# 600_V1_0.net
KiCad netlist of a schematic drawn in Altium Designer
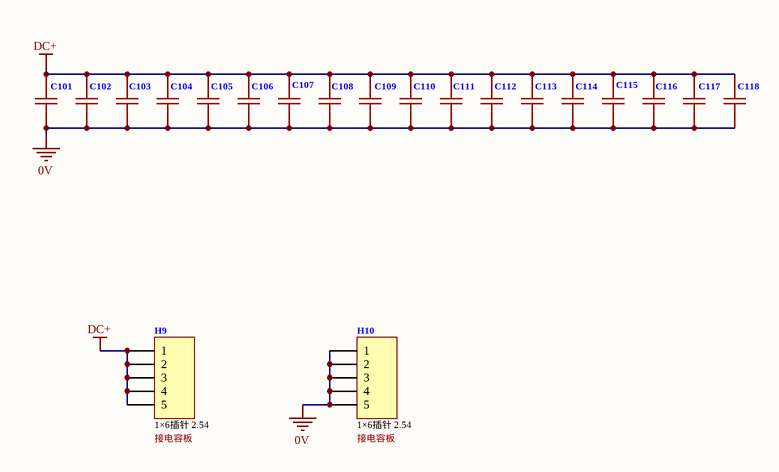
[diagram p0: 600米舵机电容板V1.0.SchDoc]

(export (version "E")
  (design (tool "Eeschema 10.0.6"))
  (components
    (comp (ref "C101")
      (value "4.7uf 100V")
      (footprint "1210_C")
      (description "贴片电容")
      (fields (field (name "MANUFACTURER") "FH(风华)") (field (name "MANUFACTURER PART") "1210B475K101NT"))
      (libsource (lib "Schlib1") (part "1210 4.7uf"))
    )
    (comp (ref "C102")
      (value "4.7uf 100V")
      (footprint "1210_C")
      (description "贴片电容")
      (fields (field (name "MANUFACTURER") "FH(风华)") (field (name "MANUFACTURER PART") "1210B475K101NT"))
      (libsource (lib "Schlib1") (part "1210 4.7uf"))
    )
    (comp (ref "C103")
      (value "4.7uf 100V")
      (footprint "1210_C")
      (description "贴片电容")
      (fields (field (name "MANUFACTURER") "FH(风华)") (field (name "MANUFACTURER PART") "1210B475K101NT"))
      (libsource (lib "Schlib1") (part "1210 4.7uf"))
    )
    (comp (ref "C104")
      (value "4.7uf 100V")
      (footprint "1210_C")
      (description "贴片电容")
      (fields (field (name "MANUFACTURER") "FH(风华)") (field (name "MANUFACTURER PART") "1210B475K101NT"))
      (libsource (lib "Schlib1") (part "1210 4.7uf"))
    )
    (comp (ref "C105")
      (value "4.7uf 100V")
      (footprint "1210_C")
      (description "贴片电容")
      (fields (field (name "MANUFACTURER") "FH(风华)") (field (name "MANUFACTURER PART") "1210B475K101NT"))
      (libsource (lib "Schlib1") (part "1210 4.7uf"))
    )
    (comp (ref "C106")
      (value "4.7uf 100V")
      (footprint "1210_C")
      (description "贴片电容")
      (fields (field (name "MANUFACTURER") "FH(风华)") (field (name "MANUFACTURER PART") "1210B475K101NT"))
      (libsource (lib "Schlib1") (part "1210 4.7uf"))
    )
    (comp (ref "C107")
      (value "4.7uf 100V")
      (footprint "1210_C")
      (description "贴片电容")
      (fields (field (name "MANUFACTURER") "FH(风华)") (field (name "MANUFACTURER PART") "1210B475K101NT"))
      (libsource (lib "Schlib1") (part "1210 4.7uf"))
    )
    (comp (ref "C108")
      (value "4.7uf 100V")
      (footprint "1210_C")
      (description "贴片电容")
      (fields (field (name "MANUFACTURER") "FH(风华)") (field (name "MANUFACTURER PART") "1210B475K101NT"))
      (libsource (lib "Schlib1") (part "1210 4.7uf"))
    )
    (comp (ref "C109")
      (value "4.7uf 100V")
      (footprint "1210_C")
      (description "贴片电容")
      (fields (field (name "MANUFACTURER") "FH(风华)") (field (name "MANUFACTURER PART") "1210B475K101NT"))
      (libsource (lib "Schlib1") (part "1210 4.7uf"))
    )
    (comp (ref "C110")
      (value "4.7uf 100V")
      (footprint "1210_C")
      (description "贴片电容")
      (fields (field (name "MANUFACTURER") "FH(风华)") (field (name "MANUFACTURER PART") "1210B475K101NT"))
      (libsource (lib "Schlib1") (part "1210 4.7uf"))
    )
    (comp (ref "C111")
      (value "4.7uf 100V")
      (footprint "1210_C")
      (description "贴片电容")
      (fields (field (name "MANUFACTURER") "FH(风华)") (field (name "MANUFACTURER PART") "1210B475K101NT"))
      (libsource (lib "Schlib1") (part "1210 4.7uf"))
    )
    (comp (ref "C112")
      (value "4.7uf 100V")
      (footprint "1210_C")
      (description "贴片电容")
      (fields (field (name "MANUFACTURER") "FH(风华)") (field (name "MANUFACTURER PART") "1210B475K101NT"))
      (libsource (lib "Schlib1") (part "1210 4.7uf"))
    )
    (comp (ref "C113")
      (value "4.7uf 100V")
      (footprint "1210_C")
      (description "贴片电容")
      (fields (field (name "MANUFACTURER") "FH(风华)") (field (name "MANUFACTURER PART") "1210B475K101NT"))
      (libsource (lib "Schlib1") (part "1210 4.7uf"))
    )
    (comp (ref "C114")
      (value "4.7uf 100V")
      (footprint "1210_C")
      (description "贴片电容")
      (fields (field (name "MANUFACTURER") "FH(风华)") (field (name "MANUFACTURER PART") "1210B475K101NT"))
      (libsource (lib "Schlib1") (part "1210 4.7uf"))
    )
    (comp (ref "C115")
      (value "4.7uf 100V")
      (footprint "1210_C")
      (description "贴片电容")
      (fields (field (name "MANUFACTURER") "FH(风华)") (field (name "MANUFACTURER PART") "1210B475K101NT"))
      (libsource (lib "Schlib1") (part "1210 4.7uf"))
    )
    (comp (ref "C116")
      (value "4.7uf 100V")
      (footprint "1210_C")
      (description "贴片电容")
      (fields (field (name "MANUFACTURER") "FH(风华)") (field (name "MANUFACTURER PART") "1210B475K101NT"))
      (libsource (lib "Schlib1") (part "1210 4.7uf"))
    )
    (comp (ref "C117")
      (value "4.7uf 100V")
      (footprint "1210_C")
      (description "贴片电容")
      (fields (field (name "MANUFACTURER") "FH(风华)") (field (name "MANUFACTURER PART") "1210B475K101NT"))
      (libsource (lib "Schlib1") (part "1210 4.7uf"))
    )
    (comp (ref "C118")
      (value "4.7uf 100V")
      (footprint "1210_C")
      (description "贴片电容")
      (fields (field (name "MANUFACTURER") "FH(风华)") (field (name "MANUFACTURER PART") "1210B475K101NT"))
      (libsource (lib "Schlib1") (part "1210 4.7uf"))
    )
    (comp (ref "H9")
      (value "1×6插针 2.54")
      (footprint "HDR1X5")
      (description "Header, 5-Pin")
      (fields (field (name "PUBLISHER") "Altium Limited"))
      (libsource (lib "Miscellaneous Connectors") (part "Header 5"))
    )
    (comp (ref "H10")
      (value "1×6插针 2.54")
      (footprint "HDR1X5")
      (description "Header, 5-Pin")
      (fields (field (name "PUBLISHER") "Altium Limited"))
      (libsource (lib "Miscellaneous Connectors") (part "Header 5"))
    )
  )
  (nets
    (net (code "1") (name "0V") (class "Default")
      (node (ref "C101") (pin "1") (pinfunction "1_1") (pintype "passive"))
      (node (ref "C102") (pin "1") (pinfunction "1_1") (pintype "passive"))
      (node (ref "C103") (pin "1") (pinfunction "1_1") (pintype "passive"))
      (node (ref "C104") (pin "1") (pinfunction "1_1") (pintype "passive"))
      (node (ref "C105") (pin "1") (pinfunction "1_1") (pintype "passive"))
      (node (ref "C106") (pin "1") (pinfunction "1_1") (pintype "passive"))
      (node (ref "C107") (pin "1") (pinfunction "1_1") (pintype "passive"))
      (node (ref "C108") (pin "1") (pinfunction "1_1") (pintype "passive"))
      (node (ref "C109") (pin "1") (pinfunction "1_1") (pintype "passive"))
      (node (ref "C110") (pin "1") (pinfunction "1_1") (pintype "passive"))
      (node (ref "C111") (pin "1") (pinfunction "1_1") (pintype "passive"))
      (node (ref "C112") (pin "1") (pinfunction "1_1") (pintype "passive"))
      (node (ref "C113") (pin "1") (pinfunction "1_1") (pintype "passive"))
      (node (ref "C114") (pin "1") (pinfunction "1_1") (pintype "passive"))
      (node (ref "C115") (pin "1") (pinfunction "1_1") (pintype "passive"))
      (node (ref "C116") (pin "1") (pinfunction "1_1") (pintype "passive"))
      (node (ref "C117") (pin "1") (pinfunction "1_1") (pintype "passive"))
      (node (ref "C118") (pin "1") (pinfunction "1_1") (pintype "passive"))
      (node (ref "H10") (pin "1") (pinfunction "1_1") (pintype "passive"))
      (node (ref "H10") (pin "2") (pinfunction "2_2") (pintype "passive"))
      (node (ref "H10") (pin "3") (pinfunction "3_3") (pintype "passive"))
      (node (ref "H10") (pin "4") (pinfunction "4_4") (pintype "passive"))
      (node (ref "H10") (pin "5") (pinfunction "5_5") (pintype "passive"))
    )
    (net (code "2") (name "DC+") (class "Default")
      (node (ref "C101") (pin "2") (pinfunction "2_2") (pintype "passive"))
      (node (ref "C102") (pin "2") (pinfunction "2_2") (pintype "passive"))
      (node (ref "C103") (pin "2") (pinfunction "2_2") (pintype "passive"))
      (node (ref "C104") (pin "2") (pinfunction "2_2") (pintype "passive"))
      (node (ref "C105") (pin "2") (pinfunction "2_2") (pintype "passive"))
      (node (ref "C106") (pin "2") (pinfunction "2_2") (pintype "passive"))
      (node (ref "C107") (pin "2") (pinfunction "2_2") (pintype "passive"))
      (node (ref "C108") (pin "2") (pinfunction "2_2") (pintype "passive"))
      (node (ref "C109") (pin "2") (pinfunction "2_2") (pintype "passive"))
      (node (ref "C110") (pin "2") (pinfunction "2_2") (pintype "passive"))
      (node (ref "C111") (pin "2") (pinfunction "2_2") (pintype "passive"))
      (node (ref "C112") (pin "2") (pinfunction "2_2") (pintype "passive"))
      (node (ref "C113") (pin "2") (pinfunction "2_2") (pintype "passive"))
      (node (ref "C114") (pin "2") (pinfunction "2_2") (pintype "passive"))
      (node (ref "C115") (pin "2") (pinfunction "2_2") (pintype "passive"))
      (node (ref "C116") (pin "2") (pinfunction "2_2") (pintype "passive"))
      (node (ref "C117") (pin "2") (pinfunction "2_2") (pintype "passive"))
      (node (ref "C118") (pin "2") (pinfunction "2_2") (pintype "passive"))
      (node (ref "H9") (pin "1") (pinfunction "1_1") (pintype "passive"))
      (node (ref "H9") (pin "2") (pinfunction "2_2") (pintype "passive"))
      (node (ref "H9") (pin "3") (pinfunction "3_3") (pintype "passive"))
      (node (ref "H9") (pin "4") (pinfunction "4_4") (pintype "passive"))
      (node (ref "H9") (pin "5") (pinfunction "5_5") (pintype "passive"))
    )
  )
)
